# 9_User_input.net
KiCad netlist of a schematic drawn in Altium Designer
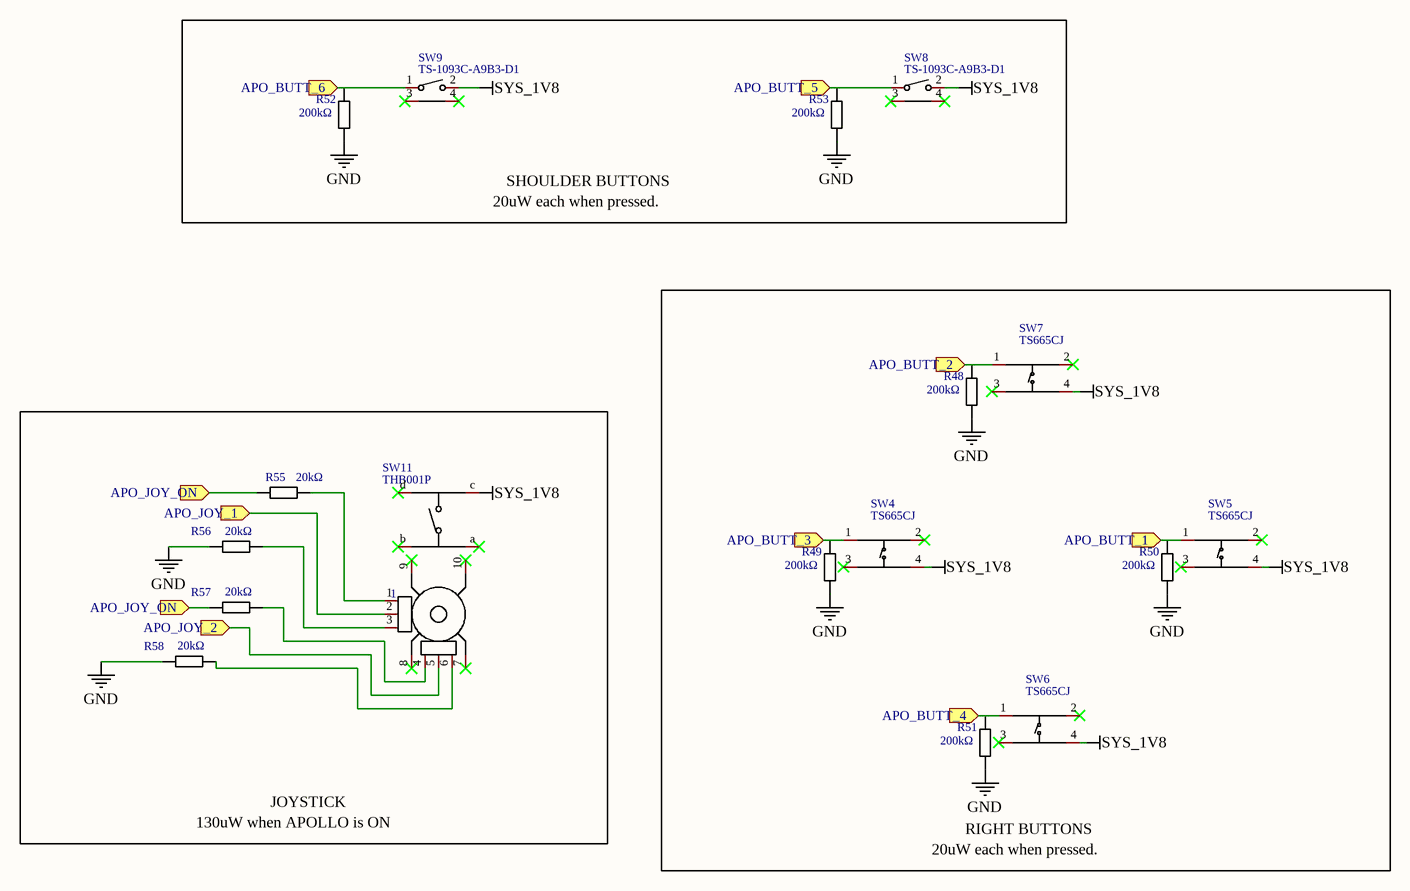
[diagram p0: 9_User input.schdoc]

(export (version "E")
  (design (tool "Eeschema 10.0.6"))
  (components
    (comp (ref "R48")
      (value "200kΩ")
      (fields
        (field (name "NAME") "200kΩ")
        (field (name "MANUFACTURER") "UniOhm")
        (field (name "MANUFACTURER PART") "0603WAF2003T5E")
      )
      (libsource (lib "altium-import") (part "root_1_0603WAF2003T5E_"))
    )
    (comp (ref "R49")
      (value "200kΩ")
      (fields
        (field (name "NAME") "200kΩ")
        (field (name "MANUFACTURER") "UniOhm")
        (field (name "MANUFACTURER PART") "0603WAF2003T5E")
      )
      (libsource (lib "altium-import") (part "root_1_0603WAF2003T5E_"))
    )
    (comp (ref "R50")
      (value "200kΩ")
      (fields
        (field (name "NAME") "200kΩ")
        (field (name "MANUFACTURER") "UniOhm")
        (field (name "MANUFACTURER PART") "0603WAF2003T5E")
      )
      (libsource (lib "altium-import") (part "root_1_0603WAF2003T5E_"))
    )
    (comp (ref "R51")
      (value "200kΩ")
      (fields
        (field (name "NAME") "200kΩ")
        (field (name "MANUFACTURER") "UniOhm")
        (field (name "MANUFACTURER PART") "0603WAF2003T5E")
      )
      (libsource (lib "altium-import") (part "root_1_0603WAF2003T5E_"))
    )
    (comp (ref "R52")
      (value "200kΩ")
      (fields
        (field (name "NAME") "200kΩ")
        (field (name "MANUFACTURER") "UniOhm")
        (field (name "MANUFACTURER PART") "0603WAF2003T5E")
      )
      (libsource (lib "altium-import") (part "root_1_0603WAF2003T5E_"))
    )
    (comp (ref "R53")
      (value "200kΩ")
      (fields
        (field (name "NAME") "200kΩ")
        (field (name "MANUFACTURER") "UniOhm")
        (field (name "MANUFACTURER PART") "0603WAF2003T5E")
      )
      (libsource (lib "altium-import") (part "root_1_0603WAF2003T5E_"))
    )
    (comp (ref "R55")
      (value "20kΩ")
      (fields
        (field (name "NAME") "20kΩ")
        (field (name "MANUFACTURER") "UniOhm")
        (field (name "MANUFACTURER PART") "0603WAF2002T5E")
      )
      (libsource (lib "altium-import") (part "root_2_0603WAF2002T5E_"))
    )
    (comp (ref "R56")
      (value "20kΩ")
      (fields
        (field (name "NAME") "20kΩ")
        (field (name "MANUFACTURER") "UniOhm")
        (field (name "MANUFACTURER PART") "0603WAF2002T5E")
      )
      (libsource (lib "altium-import") (part "root_2_0603WAF2002T5E_"))
    )
    (comp (ref "R57")
      (value "20kΩ")
      (fields
        (field (name "NAME") "20kΩ")
        (field (name "MANUFACTURER") "UniOhm")
        (field (name "MANUFACTURER PART") "0603WAF2002T5E")
      )
      (libsource (lib "altium-import") (part "root_2_0603WAF2002T5E_"))
    )
    (comp (ref "R58")
      (value "20kΩ")
      (fields
        (field (name "NAME") "20kΩ")
        (field (name "MANUFACTURER") "UniOhm")
        (field (name "MANUFACTURER PART") "0603WAF2002T5E")
      )
      (libsource (lib "altium-import") (part "root_2_0603WAF2002T5E_"))
    )
    (comp (ref "SW4")
      (value "TS665CJ")
      (fields (field (name "NAME") "TS665CJ") (field (name "MANUFACTURER") "SHOU HAN"))
      (libsource (lib "altium-import") (part "root_0_TS665CJ_"))
    )
    (comp (ref "SW5")
      (value "TS665CJ")
      (fields (field (name "NAME") "TS665CJ") (field (name "MANUFACTURER") "SHOU HAN"))
      (libsource (lib "altium-import") (part "root_0_TS665CJ_"))
    )
    (comp (ref "SW6")
      (value "TS665CJ")
      (fields (field (name "NAME") "TS665CJ") (field (name "MANUFACTURER") "SHOU HAN"))
      (libsource (lib "altium-import") (part "root_0_TS665CJ_"))
    )
    (comp (ref "SW7")
      (value "TS665CJ")
      (fields (field (name "NAME") "TS665CJ") (field (name "MANUFACTURER") "SHOU HAN"))
      (libsource (lib "altium-import") (part "root_0_TS665CJ_"))
    )
    (comp (ref "SW8")
      (value "TS-1093C-A9B3-D1")
      (fields (field (name "NAME") "TS-1093C-A9B3-D1") (field (name "MANUFACTURER") "Yuandi"))
      (libsource (lib "altium-import") (part "root_0_TS-1093C-A9B3-D1_"))
    )
    (comp (ref "SW9")
      (value "TS-1093C-A9B3-D1")
      (fields (field (name "NAME") "TS-1093C-A9B3-D1") (field (name "MANUFACTURER") "Yuandi"))
      (libsource (lib "altium-import") (part "root_0_TS-1093C-A9B3-D1_"))
    )
    (comp (ref "SW11")
      (value "THB001P")
      (fields (field (name "NAME") "THB001P") (field (name "MANUFACTURER") "C&K") (field (name "NUMBER") "1"))
      (libsource (lib "altium-import") (part "root_2_THB001P_"))
    )
  )
  (nets
    (net (code "1") (name "/APO_BUTT_1") (class "Default")
      (node (ref "R50") (pin "2") (pinfunction "2_2") (pintype "passive"))
      (node (ref "SW5") (pin "1") (pinfunction "A_1") (pintype "passive"))
    )
    (net (code "2") (name "/APO_BUTT_2") (class "Default")
      (node (ref "R48") (pin "2") (pinfunction "2_2") (pintype "passive"))
      (node (ref "SW7") (pin "1") (pinfunction "A_1") (pintype "passive"))
    )
    (net (code "3") (name "/APO_BUTT_3") (class "Default")
      (node (ref "R49") (pin "2") (pinfunction "2_2") (pintype "passive"))
      (node (ref "SW4") (pin "1") (pinfunction "A_1") (pintype "passive"))
    )
    (net (code "4") (name "/APO_BUTT_4") (class "Default")
      (node (ref "R51") (pin "2") (pinfunction "2_2") (pintype "passive"))
      (node (ref "SW6") (pin "1") (pinfunction "A_1") (pintype "passive"))
    )
    (net (code "5") (name "/APO_BUTT_5") (class "Default")
      (node (ref "R53") (pin "2") (pinfunction "2_2") (pintype "passive"))
      (node (ref "SW8") (pin "1") (pinfunction "1_1") (pintype "passive"))
    )
    (net (code "6") (name "/APO_BUTT_6") (class "Default")
      (node (ref "R52") (pin "2") (pinfunction "2_2") (pintype "passive"))
      (node (ref "SW9") (pin "1") (pinfunction "1_1") (pintype "passive"))
    )
    (net (code "7") (name "/APO_JOY_1") (class "Default")
      (node (ref "SW11") (pin "2") (pinfunction "DTA_2") (pintype "passive"))
    )
    (net (code "8") (name "/APO_JOY_2") (class "Default")
      (node (ref "SW11") (pin "5") (pinfunction "DTA_5") (pintype "passive"))
    )
    (net (code "9") (name "/APO_JOY_ON") (class "Default")
      (node (ref "R55") (pin "2") (pinfunction "2_2") (pintype "passive"))
      (node (ref "R57") (pin "2") (pinfunction "2_2") (pintype "passive"))
    )
    (net (code "10") (name "GND") (class "Default")
      (node (ref "R48") (pin "1") (pinfunction "1_1") (pintype "passive"))
      (node (ref "R49") (pin "1") (pinfunction "1_1") (pintype "passive"))
      (node (ref "R50") (pin "1") (pinfunction "1_1") (pintype "passive"))
      (node (ref "R51") (pin "1") (pinfunction "1_1") (pintype "passive"))
      (node (ref "R52") (pin "1") (pinfunction "1_1") (pintype "passive"))
      (node (ref "R53") (pin "1") (pinfunction "1_1") (pintype "passive"))
      (node (ref "R56") (pin "2") (pinfunction "2_2") (pintype "passive"))
      (node (ref "R58") (pin "2") (pinfunction "2_2") (pintype "passive"))
    )
    (net (code "11") (name "Net-(R55-Pad1)") (class "Default")
      (node (ref "R55") (pin "1") (pinfunction "1_1") (pintype "passive"))
      (node (ref "SW11") (pin "1") (pinfunction "B_1") (pintype "passive"))
    )
    (net (code "12") (name "Net-(R56-Pad1)") (class "Default")
      (node (ref "R56") (pin "1") (pinfunction "1_1") (pintype "passive"))
      (node (ref "SW11") (pin "3") (pinfunction "A_3") (pintype "passive"))
    )
    (net (code "13") (name "Net-(R57-Pad1)") (class "Default")
      (node (ref "R57") (pin "1") (pinfunction "1_1") (pintype "passive"))
      (node (ref "SW11") (pin "4") (pinfunction "A_4") (pintype "passive"))
    )
    (net (code "14") (name "Net-(R58-Pad1)") (class "Default")
      (node (ref "R58") (pin "1") (pinfunction "1_1") (pintype "passive"))
      (node (ref "SW11") (pin "6") (pinfunction "B_6") (pintype "passive"))
    )
    (net (code "15") (name "SYS_1V8") (class "Default")
      (node (ref "SW11") (pin "c") (pinfunction "c_c") (pintype "passive"))
      (node (ref "SW4") (pin "4") (pinfunction "D_4") (pintype "passive"))
      (node (ref "SW5") (pin "4") (pinfunction "D_4") (pintype "passive"))
      (node (ref "SW6") (pin "4") (pinfunction "D_4") (pintype "passive"))
      (node (ref "SW7") (pin "4") (pinfunction "D_4") (pintype "passive"))
      (node (ref "SW8") (pin "2") (pinfunction "2_2") (pintype "passive"))
      (node (ref "SW9") (pin "2") (pinfunction "2_2") (pintype "passive"))
    )
    (net (code "16") (name "unconnected-(SW4-B-Pad2)") (class "Default")
      (node (ref "SW4") (pin "2") (pinfunction "B_2") (pintype "passive+no_connect"))
    )
    (net (code "17") (name "unconnected-(SW4-C-Pad3)") (class "Default")
      (node (ref "SW4") (pin "3") (pinfunction "C_3") (pintype "passive+no_connect"))
    )
    (net (code "18") (name "unconnected-(SW5-B-Pad2)") (class "Default")
      (node (ref "SW5") (pin "2") (pinfunction "B_2") (pintype "passive+no_connect"))
    )
    (net (code "19") (name "unconnected-(SW5-C-Pad3)") (class "Default")
      (node (ref "SW5") (pin "3") (pinfunction "C_3") (pintype "passive+no_connect"))
    )
    (net (code "20") (name "unconnected-(SW6-B-Pad2)") (class "Default")
      (node (ref "SW6") (pin "2") (pinfunction "B_2") (pintype "passive+no_connect"))
    )
    (net (code "21") (name "unconnected-(SW6-C-Pad3)") (class "Default")
      (node (ref "SW6") (pin "3") (pinfunction "C_3") (pintype "passive+no_connect"))
    )
    (net (code "22") (name "unconnected-(SW7-B-Pad2)") (class "Default")
      (node (ref "SW7") (pin "2") (pinfunction "B_2") (pintype "passive+no_connect"))
    )
    (net (code "23") (name "unconnected-(SW7-C-Pad3)") (class "Default")
      (node (ref "SW7") (pin "3") (pinfunction "C_3") (pintype "passive+no_connect"))
    )
    (net (code "24") (name "unconnected-(SW8-EP-Pad3)") (class "Default")
      (node (ref "SW8") (pin "3") (pinfunction "EP_3") (pintype "passive+no_connect"))
    )
    (net (code "25") (name "unconnected-(SW8-EP-Pad4)") (class "Default")
      (node (ref "SW8") (pin "4") (pinfunction "EP_4") (pintype "passive+no_connect"))
    )
    (net (code "26") (name "unconnected-(SW9-EP-Pad3)") (class "Default")
      (node (ref "SW9") (pin "3") (pinfunction "EP_3") (pintype "passive+no_connect"))
    )
    (net (code "27") (name "unconnected-(SW9-EP-Pad4)") (class "Default")
      (node (ref "SW9") (pin "4") (pinfunction "EP_4") (pintype "passive+no_connect"))
    )
    (net (code "28") (name "unconnected-(SW11-GND-Pad7)") (class "Default")
      (node (ref "SW11") (pin "7") (pinfunction "GND_7") (pintype "passive+no_connect"))
    )
    (net (code "29") (name "unconnected-(SW11-GND-Pad8)") (class "Default")
      (node (ref "SW11") (pin "8") (pinfunction "GND_8") (pintype "passive+no_connect"))
    )
    (net (code "30") (name "unconnected-(SW11-GND-Pad9)") (class "Default")
      (node (ref "SW11") (pin "9") (pinfunction "GND_9") (pintype "passive+no_connect"))
    )
    (net (code "31") (name "unconnected-(SW11-GND-Pad10)") (class "Default")
      (node (ref "SW11") (pin "10") (pinfunction "GND_10") (pintype "passive+no_connect"))
    )
    (net (code "32") (name "unconnected-(SW11-Pada)") (class "Default")
      (node (ref "SW11") (pin "a") (pinfunction "a_a") (pintype "passive+no_connect"))
    )
    (net (code "33") (name "unconnected-(SW11-Padb)") (class "Default")
      (node (ref "SW11") (pin "b") (pinfunction "b_b") (pintype "passive+no_connect"))
    )
    (net (code "34") (name "unconnected-(SW11-Padd)") (class "Default")
      (node (ref "SW11") (pin "d") (pinfunction "d_d") (pintype "passive+no_connect"))
    )
  )
)
